# LFO.net
KiCad netlist of a schematic drawn in EAGLE
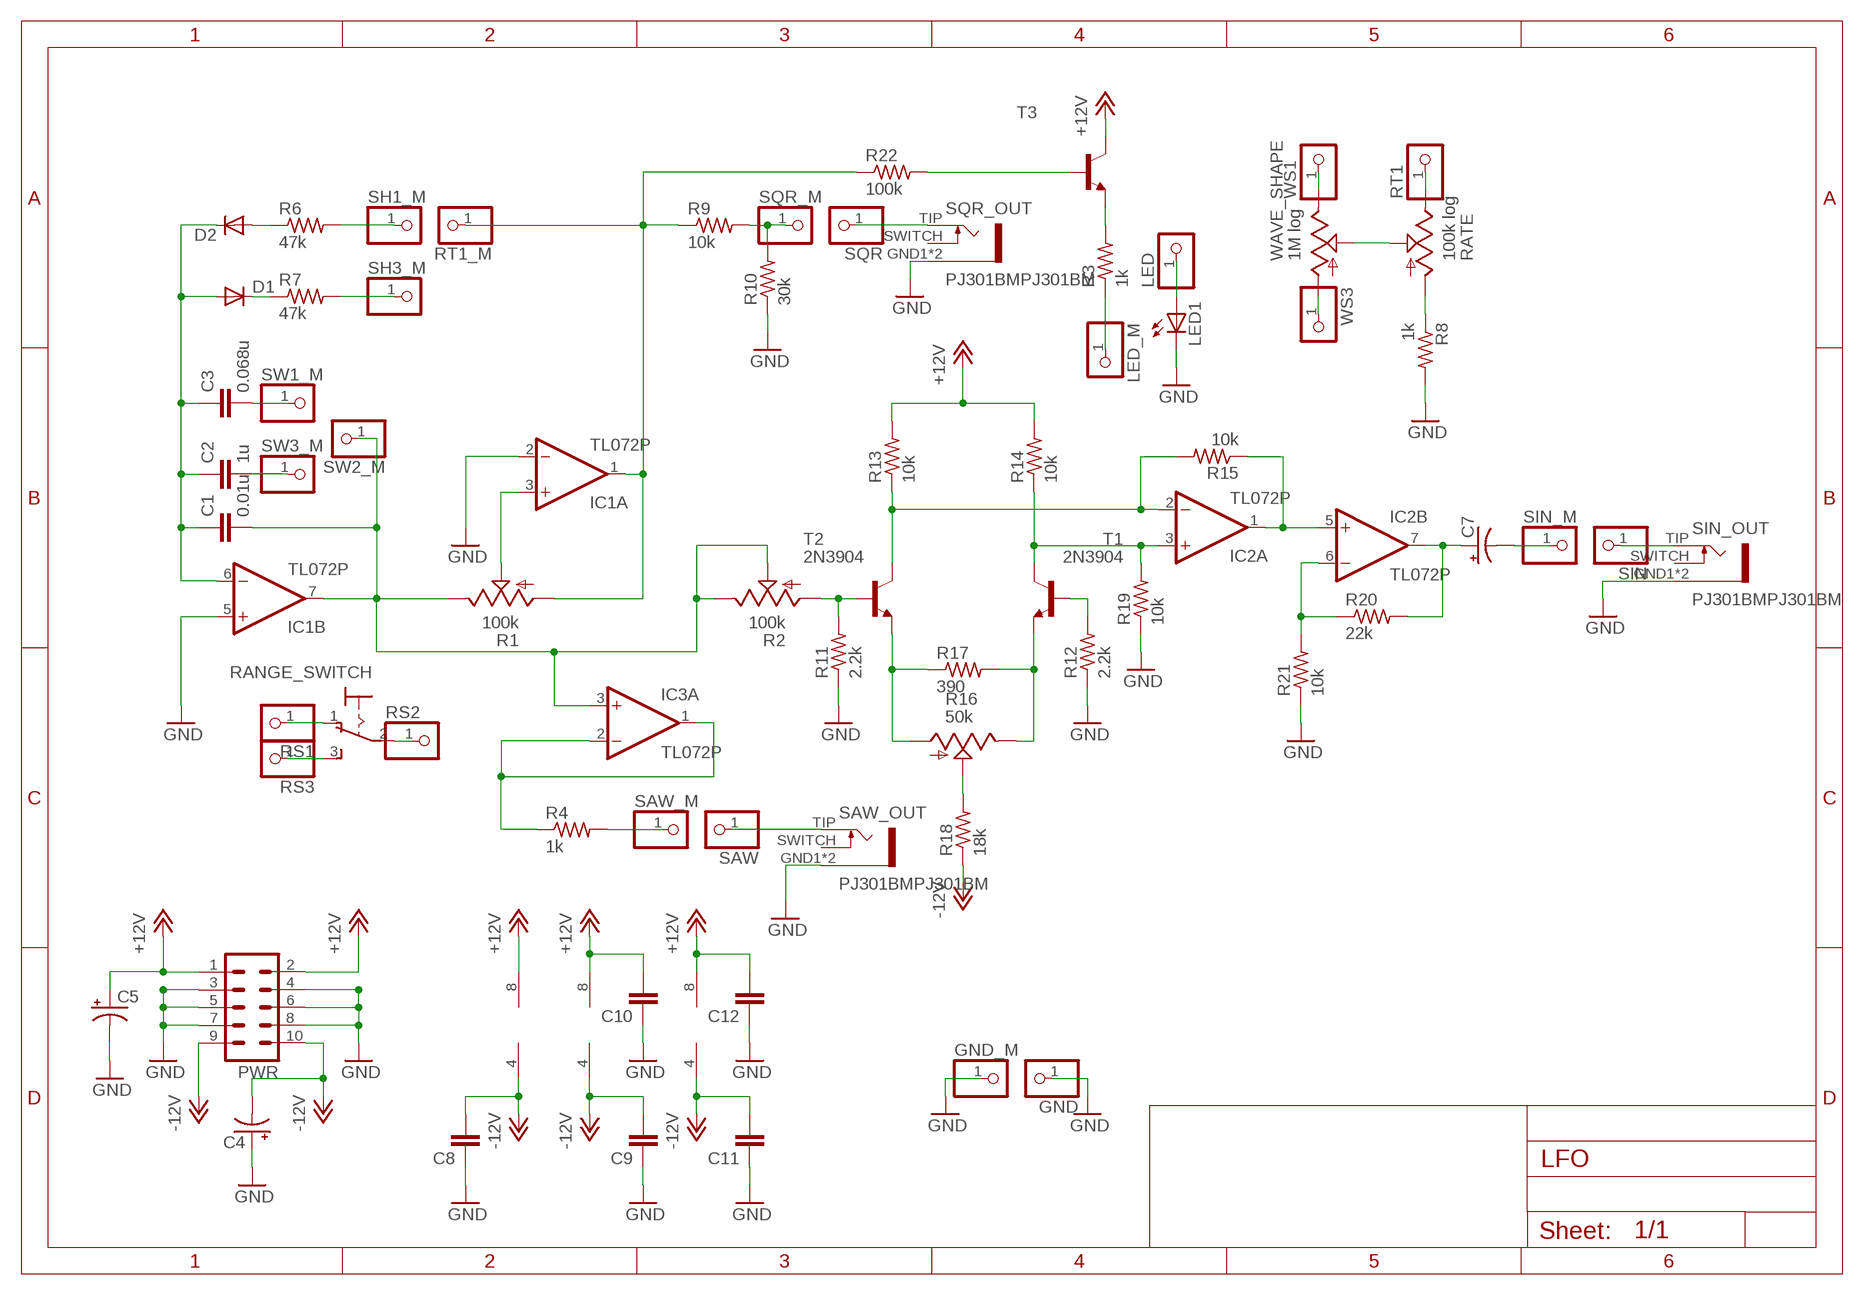
[diagram p0: schematic, sheet 1]

(export (version "E")
  (design (tool "Eeschema 10.0.6"))
  (components
    (comp (ref "C1")
      (value "0.01u")
      (footprint "eagle-import:C050-025X075")
      (libsource (lib "eagle-import") (part "C-EU050-025X075"))
    )
    (comp (ref "C2")
      (value "1u")
      (footprint "eagle-import:C050-025X075")
      (libsource (lib "eagle-import") (part "C-EU050-025X075"))
    )
    (comp (ref "C3")
      (value "0.068u")
      (footprint "eagle-import:C050-025X075")
      (libsource (lib "eagle-import") (part "C-EU050-025X075"))
    )
    (comp (ref "C4")
      (value "CPOL-USE2.5-5")
      (footprint "eagle-import:E2,5-5")
      (libsource (lib "eagle-import") (part "CPOL-USE2.5-5"))
    )
    (comp (ref "C5")
      (value "CPOL-USE2.5-5")
      (footprint "eagle-import:E2,5-5")
      (libsource (lib "eagle-import") (part "CPOL-USE2.5-5"))
    )
    (comp (ref "C7")
      (value "CPOL-USE2.5-5")
      (footprint "eagle-import:E2,5-5")
      (libsource (lib "eagle-import") (part "CPOL-USE2.5-5"))
    )
    (comp (ref "C8")
      (value "C-EU025-024X044")
      (footprint "eagle-import:C025-024X044")
      (libsource (lib "eagle-import") (part "C-EU025-024X044"))
    )
    (comp (ref "C9")
      (value "C-EU025-024X044")
      (footprint "eagle-import:C025-024X044")
      (libsource (lib "eagle-import") (part "C-EU025-024X044"))
    )
    (comp (ref "C10")
      (value "C-EU025-024X044")
      (footprint "eagle-import:C025-024X044")
      (libsource (lib "eagle-import") (part "C-EU025-024X044"))
    )
    (comp (ref "C11")
      (value "C-EU025-024X044")
      (footprint "eagle-import:C025-024X044")
      (libsource (lib "eagle-import") (part "C-EU025-024X044"))
    )
    (comp (ref "C12")
      (value "C-EU025-024X044")
      (footprint "eagle-import:C025-024X044")
      (libsource (lib "eagle-import") (part "C-EU025-024X044"))
    )
    (comp (ref "D1")
      (value "1N4148DO35-7")
      (footprint "eagle-import:DO35-7")
      (libsource (lib "eagle-import") (part "1N4148DO35-7"))
    )
    (comp (ref "D2")
      (value "1N4148DO35-7")
      (footprint "eagle-import:DO35-7")
      (libsource (lib "eagle-import") (part "1N4148DO35-7"))
    )
    (comp (ref "GND")
      (value "PINHD-1X1")
      (footprint "eagle-import:1X01")
      (libsource (lib "eagle-import") (part "PINHD-1X1"))
    )
    (comp (ref "GND_M")
      (value "PINHD-1X1")
      (footprint "eagle-import:1X01")
      (libsource (lib "eagle-import") (part "PINHD-1X1"))
    )
    (comp (ref "IC1")
      (value "TL072P")
      (footprint "eagle-import:DIL08")
      (libsource (lib "eagle-import") (part "TL072P"))
    )
    (comp (ref "IC2")
      (value "TL072P")
      (footprint "eagle-import:DIL08")
      (libsource (lib "eagle-import") (part "TL072P"))
    )
    (comp (ref "IC3")
      (value "TL072P")
      (footprint "eagle-import:DIL08")
      (libsource (lib "eagle-import") (part "TL072P"))
    )
    (comp (ref "LED")
      (value "PINHD-1X1")
      (footprint "eagle-import:1X01")
      (libsource (lib "eagle-import") (part "PINHD-1X1"))
    )
    (comp (ref "LED1")
      (value "LED5MM")
      (footprint "eagle-import:LED5MM")
      (libsource (lib "eagle-import") (part "LED5MM"))
    )
    (comp (ref "LED_M")
      (value "PINHD-1X1")
      (footprint "eagle-import:1X01")
      (libsource (lib "eagle-import") (part "PINHD-1X1"))
    )
    (comp (ref "PWR")
      (value "ML10")
      (footprint "eagle-import:ML10")
      (libsource (lib "eagle-import") (part "ML10"))
    )
    (comp (ref "R1")
      (value "100k")
      (footprint "eagle-import:RJ9W")
      (libsource (lib "eagle-import") (part "TRIM_US-RJ9W"))
    )
    (comp (ref "R2")
      (value "100k")
      (footprint "eagle-import:RJ9W")
      (libsource (lib "eagle-import") (part "TRIM_US-RJ9W"))
    )
    (comp (ref "R3")
      (value "1k")
      (footprint "eagle-import:0207_10")
      (libsource (lib "eagle-import") (part "R-US_0207/10"))
    )
    (comp (ref "R4")
      (value "1k")
      (footprint "eagle-import:0207_2V")
      (libsource (lib "eagle-import") (part "R-US_0207/2V"))
    )
    (comp (ref "R6")
      (value "47k")
      (footprint "eagle-import:0207_10")
      (libsource (lib "eagle-import") (part "R-US_0207/10"))
    )
    (comp (ref "R7")
      (value "47k")
      (footprint "eagle-import:0207_10")
      (libsource (lib "eagle-import") (part "R-US_0207/10"))
    )
    (comp (ref "R8")
      (value "1k")
      (footprint "eagle-import:0207_10")
      (libsource (lib "eagle-import") (part "R-US_0207/10"))
    )
    (comp (ref "R9")
      (value "10k")
      (footprint "eagle-import:0207_10")
      (libsource (lib "eagle-import") (part "R-US_0207/10"))
    )
    (comp (ref "R10")
      (value "30k")
      (footprint "eagle-import:0207_10")
      (libsource (lib "eagle-import") (part "R-US_0207/10"))
    )
    (comp (ref "R11")
      (value "2.2k")
      (footprint "eagle-import:0207_10")
      (libsource (lib "eagle-import") (part "R-US_0207/10"))
    )
    (comp (ref "R12")
      (value "2.2k")
      (footprint "eagle-import:0207_10")
      (libsource (lib "eagle-import") (part "R-US_0207/10"))
    )
    (comp (ref "R13")
      (value "10k")
      (footprint "eagle-import:0207_10")
      (libsource (lib "eagle-import") (part "R-US_0207/10"))
    )
    (comp (ref "R14")
      (value "10k")
      (footprint "eagle-import:0207_2V")
      (libsource (lib "eagle-import") (part "R-US_0207/2V"))
    )
    (comp (ref "R15")
      (value "10k")
      (footprint "eagle-import:0207_2V")
      (libsource (lib "eagle-import") (part "R-US_0207/2V"))
    )
    (comp (ref "R16")
      (value "50k")
      (footprint "eagle-import:RJ9W")
      (libsource (lib "eagle-import") (part "TRIM_US-RJ9W"))
    )
    (comp (ref "R17")
      (value "390")
      (footprint "eagle-import:0207_10")
      (libsource (lib "eagle-import") (part "R-US_0207/10"))
    )
    (comp (ref "R18")
      (value "18k")
      (footprint "eagle-import:0207_10")
      (libsource (lib "eagle-import") (part "R-US_0207/10"))
    )
    (comp (ref "R19")
      (value "10k")
      (footprint "eagle-import:0207_2V")
      (libsource (lib "eagle-import") (part "R-US_0207/2V"))
    )
    (comp (ref "R20")
      (value "22k")
      (footprint "eagle-import:0207_2V")
      (libsource (lib "eagle-import") (part "R-US_0207/2V"))
    )
    (comp (ref "R21")
      (value "10k")
      (footprint "eagle-import:0207_2V")
      (libsource (lib "eagle-import") (part "R-US_0207/2V"))
    )
    (comp (ref "R22")
      (value "100k")
      (footprint "eagle-import:0207_10")
      (libsource (lib "eagle-import") (part "R-US_0207/10"))
    )
    (comp (ref "RANGE_SWITCH")
      (value "M9040P")
      (footprint "eagle-import:M9040P")
      (libsource (lib "eagle-import") (part "M9040P"))
    )
    (comp (ref "RATE")
      (value "100k log")
      (footprint "eagle-import:EVUF")
      (libsource (lib "eagle-import") (part "ALPHA-9MMA"))
    )
    (comp (ref "RS1")
      (value "PINHD-1X1")
      (footprint "eagle-import:1X01")
      (libsource (lib "eagle-import") (part "PINHD-1X1"))
    )
    (comp (ref "RS2")
      (value "PINHD-1X1")
      (footprint "eagle-import:1X01")
      (libsource (lib "eagle-import") (part "PINHD-1X1"))
    )
    (comp (ref "RS3")
      (value "PINHD-1X1")
      (footprint "eagle-import:1X01")
      (libsource (lib "eagle-import") (part "PINHD-1X1"))
    )
    (comp (ref "RT1")
      (value "PINHD-1X1")
      (footprint "eagle-import:1X01")
      (libsource (lib "eagle-import") (part "PINHD-1X1"))
    )
    (comp (ref "RT1_M")
      (value "PINHD-1X1")
      (footprint "eagle-import:1X01")
      (libsource (lib "eagle-import") (part "PINHD-1X1"))
    )
    (comp (ref "SAW")
      (value "PINHD-1X1")
      (footprint "eagle-import:1X01")
      (libsource (lib "eagle-import") (part "PINHD-1X1"))
    )
    (comp (ref "SAW_M")
      (value "PINHD-1X1")
      (footprint "eagle-import:1X01")
      (libsource (lib "eagle-import") (part "PINHD-1X1"))
    )
    (comp (ref "SAW_OUT")
      (value "PJ301BMPJ301BM")
      (footprint "eagle-import:PJ301BM")
      (libsource (lib "eagle-import") (part "PJ301BMPJ301BM"))
    )
    (comp (ref "SH1_M")
      (value "PINHD-1X1")
      (footprint "eagle-import:1X01")
      (libsource (lib "eagle-import") (part "PINHD-1X1"))
    )
    (comp (ref "SH3_M")
      (value "PINHD-1X1")
      (footprint "eagle-import:1X01")
      (libsource (lib "eagle-import") (part "PINHD-1X1"))
    )
    (comp (ref "SIN")
      (value "PINHD-1X1")
      (footprint "eagle-import:1X01")
      (libsource (lib "eagle-import") (part "PINHD-1X1"))
    )
    (comp (ref "SIN_M")
      (value "PINHD-1X1")
      (footprint "eagle-import:1X01")
      (libsource (lib "eagle-import") (part "PINHD-1X1"))
    )
    (comp (ref "SIN_OUT")
      (value "PJ301BMPJ301BM")
      (footprint "eagle-import:PJ301BM")
      (libsource (lib "eagle-import") (part "PJ301BMPJ301BM"))
    )
    (comp (ref "SQR")
      (value "PINHD-1X1")
      (footprint "eagle-import:1X01")
      (libsource (lib "eagle-import") (part "PINHD-1X1"))
    )
    (comp (ref "SQR_M")
      (value "PINHD-1X1")
      (footprint "eagle-import:1X01")
      (libsource (lib "eagle-import") (part "PINHD-1X1"))
    )
    (comp (ref "SQR_OUT")
      (value "PJ301BMPJ301BM")
      (footprint "eagle-import:PJ301BM")
      (libsource (lib "eagle-import") (part "PJ301BMPJ301BM"))
    )
    (comp (ref "SW1_M")
      (value "PINHD-1X1")
      (footprint "eagle-import:1X01")
      (libsource (lib "eagle-import") (part "PINHD-1X1"))
    )
    (comp (ref "SW2_M")
      (value "PINHD-1X1")
      (footprint "eagle-import:1X01")
      (libsource (lib "eagle-import") (part "PINHD-1X1"))
    )
    (comp (ref "SW3_M")
      (value "PINHD-1X1")
      (footprint "eagle-import:1X01")
      (libsource (lib "eagle-import") (part "PINHD-1X1"))
    )
    (comp (ref "T1")
      (value "2N3904")
      (footprint "eagle-import:TO92")
      (libsource (lib "eagle-import") (part "2N3904"))
    )
    (comp (ref "T2")
      (value "2N3904")
      (footprint "eagle-import:TO92")
      (libsource (lib "eagle-import") (part "2N3904"))
    )
    (comp (ref "T3")
      (value "BC550-NPN-TO92-CBE")
      (footprint "eagle-import:TO92-CBE")
      (libsource (lib "eagle-import") (part "-NPN-TO92-CBEBC550"))
    )
    (comp (ref "WAVE_SHAPE")
      (value "1M log")
      (footprint "eagle-import:EVUF")
      (libsource (lib "eagle-import") (part "ALPHA-9MMA"))
    )
    (comp (ref "WS1")
      (value "PINHD-1X1")
      (footprint "eagle-import:1X01")
      (libsource (lib "eagle-import") (part "PINHD-1X1"))
    )
    (comp (ref "WS3")
      (value "PINHD-1X1")
      (footprint "eagle-import:1X01")
      (libsource (lib "eagle-import") (part "PINHD-1X1"))
    )
  )
  (nets
    (net (code "1") (name "+12V") (class "Default")
      (node (ref "C10") (pin "2") (pinfunction "2_2") (pintype "passive"))
      (node (ref "C12") (pin "2") (pinfunction "2_2") (pintype "passive"))
      (node (ref "C5") (pin "+") (pinfunction "+_+") (pintype "passive"))
      (node (ref "IC1") (pin "8") (pinfunction "V+_8") (pintype "power_in"))
      (node (ref "IC2") (pin "8") (pinfunction "V+_8") (pintype "power_in"))
      (node (ref "IC3") (pin "8") (pinfunction "V+_8") (pintype "power_in"))
      (node (ref "PWR") (pin "1") (pinfunction "1_1") (pintype "passive"))
      (node (ref "PWR") (pin "2") (pinfunction "2_2") (pintype "passive"))
      (node (ref "R13") (pin "2") (pinfunction "2_2") (pintype "passive"))
      (node (ref "R14") (pin "2") (pinfunction "2_2") (pintype "passive"))
      (node (ref "T3") (pin "C") (pinfunction "C_C") (pintype "passive"))
    )
    (net (code "2") (name "-12V") (class "Default")
      (node (ref "C11") (pin "2") (pinfunction "2_2") (pintype "passive"))
      (node (ref "C4") (pin "-") (pinfunction "-_-") (pintype "passive"))
      (node (ref "C8") (pin "2") (pinfunction "2_2") (pintype "passive"))
      (node (ref "C9") (pin "2") (pinfunction "2_2") (pintype "passive"))
      (node (ref "IC1") (pin "4") (pinfunction "V-_4") (pintype "power_in"))
      (node (ref "IC2") (pin "4") (pinfunction "V-_4") (pintype "power_in"))
      (node (ref "IC3") (pin "4") (pinfunction "V-_4") (pintype "power_in"))
      (node (ref "PWR") (pin "10") (pinfunction "10_10") (pintype "passive"))
      (node (ref "PWR") (pin "9") (pinfunction "9_9") (pintype "passive"))
      (node (ref "R18") (pin "1") (pinfunction "1_1") (pintype "passive"))
    )
    (net (code "3") (name "GND") (class "Default")
      (node (ref "C10") (pin "1") (pinfunction "1_1") (pintype "passive"))
      (node (ref "C11") (pin "1") (pinfunction "1_1") (pintype "passive"))
      (node (ref "C12") (pin "1") (pinfunction "1_1") (pintype "passive"))
      (node (ref "C4") (pin "+") (pinfunction "+_+") (pintype "passive"))
      (node (ref "C5") (pin "-") (pinfunction "-_-") (pintype "passive"))
      (node (ref "C8") (pin "1") (pinfunction "1_1") (pintype "passive"))
      (node (ref "C9") (pin "1") (pinfunction "1_1") (pintype "passive"))
      (node (ref "GND") (pin "1") (pinfunction "1_1") (pintype "passive"))
      (node (ref "GND_M") (pin "1") (pinfunction "1_1") (pintype "passive"))
      (node (ref "IC1") (pin "2") (pinfunction "-IN_2") (pintype "input"))
      (node (ref "IC1") (pin "5") (pinfunction "+IN_5") (pintype "input"))
      (node (ref "LED1") (pin "K") (pinfunction "C_K") (pintype "passive"))
      (node (ref "PWR") (pin "3") (pinfunction "3_3") (pintype "passive"))
      (node (ref "PWR") (pin "4") (pinfunction "4_4") (pintype "passive"))
      (node (ref "PWR") (pin "5") (pinfunction "5_5") (pintype "passive"))
      (node (ref "PWR") (pin "6") (pinfunction "6_6") (pintype "passive"))
      (node (ref "PWR") (pin "7") (pinfunction "7_7") (pintype "passive"))
      (node (ref "PWR") (pin "8") (pinfunction "8_8") (pintype "passive"))
      (node (ref "R10") (pin "1") (pinfunction "1_1") (pintype "passive"))
      (node (ref "R11") (pin "1") (pinfunction "1_1") (pintype "passive"))
      (node (ref "R12") (pin "1") (pinfunction "1_1") (pintype "passive"))
      (node (ref "R19") (pin "1") (pinfunction "1_1") (pintype "passive"))
      (node (ref "R21") (pin "1") (pinfunction "1_1") (pintype "passive"))
      (node (ref "R8") (pin "2") (pinfunction "2_2") (pintype "passive"))
      (node (ref "SAW_OUT") (pin "GND1") (pinfunction "5_GND1") (pintype "passive"))
      (node (ref "SAW_OUT") (pin "GND2") (pinfunction "5_GND2") (pintype "passive"))
      (node (ref "SIN_OUT") (pin "GND1") (pinfunction "5_GND1") (pintype "passive"))
      (node (ref "SIN_OUT") (pin "GND2") (pinfunction "5_GND2") (pintype "passive"))
      (node (ref "SQR_OUT") (pin "GND1") (pinfunction "5_GND1") (pintype "passive"))
      (node (ref "SQR_OUT") (pin "GND2") (pinfunction "5_GND2") (pintype "passive"))
    )
    (net (code "4") (name "Net-(C2-Pad2)") (class "Default")
      (node (ref "C2") (pin "2") (pinfunction "2_2") (pintype "passive"))
      (node (ref "SW3_M") (pin "1") (pinfunction "1_1") (pintype "passive"))
    )
    (net (code "5") (name "Net-(C3-Pad2)") (class "Default")
      (node (ref "C3") (pin "2") (pinfunction "2_2") (pintype "passive"))
      (node (ref "SW1_M") (pin "1") (pinfunction "1_1") (pintype "passive"))
    )
    (net (code "6") (name "Net-(C7-Pad-)") (class "Default")
      (node (ref "C7") (pin "-") (pinfunction "-_-") (pintype "passive"))
      (node (ref "SIN_M") (pin "1") (pinfunction "1_1") (pintype "passive"))
    )
    (net (code "7") (name "Net-(D1-PadC)") (class "Default")
      (node (ref "D1") (pin "C") (pinfunction "C_C") (pintype "passive"))
      (node (ref "R7") (pin "1") (pinfunction "1_1") (pintype "passive"))
    )
    (net (code "8") (name "Net-(D2-PadA)") (class "Default")
      (node (ref "D2") (pin "A") (pinfunction "A_A") (pintype "passive"))
      (node (ref "R6") (pin "1") (pinfunction "1_1") (pintype "passive"))
    )
    (net (code "9") (name "Net-(IC1A-+IN)") (class "Default")
      (node (ref "IC1") (pin "3") (pinfunction "+IN_3") (pintype "input"))
      (node (ref "R1") (pin "S") (pinfunction "S_S") (pintype "passive"))
    )
    (net (code "10") (name "Net-(IC1A-OUT)") (class "Default")
      (node (ref "IC1") (pin "1") (pinfunction "OUT_1") (pintype "output"))
      (node (ref "R1") (pin "A") (pinfunction "A_A") (pintype "passive"))
      (node (ref "R22") (pin "1") (pinfunction "1_1") (pintype "passive"))
      (node (ref "R9") (pin "1") (pinfunction "1_1") (pintype "passive"))
      (node (ref "RT1_M") (pin "1") (pinfunction "1_1") (pintype "passive"))
    )
    (net (code "11") (name "Net-(IC1B--IN)") (class "Default")
      (node (ref "C1") (pin "1") (pinfunction "1_1") (pintype "passive"))
      (node (ref "C2") (pin "1") (pinfunction "1_1") (pintype "passive"))
      (node (ref "C3") (pin "1") (pinfunction "1_1") (pintype "passive"))
      (node (ref "D1") (pin "A") (pinfunction "A_A") (pintype "passive"))
      (node (ref "D2") (pin "C") (pinfunction "C_C") (pintype "passive"))
      (node (ref "IC1") (pin "6") (pinfunction "-IN_6") (pintype "input"))
    )
    (net (code "12") (name "Net-(IC1B-OUT)") (class "Default")
      (node (ref "C1") (pin "2") (pinfunction "2_2") (pintype "passive"))
      (node (ref "IC1") (pin "7") (pinfunction "OUT_7") (pintype "output"))
      (node (ref "IC3") (pin "3") (pinfunction "+IN_3") (pintype "input"))
      (node (ref "R1") (pin "E") (pinfunction "E_E") (pintype "passive"))
      (node (ref "R2") (pin "E") (pinfunction "E_E") (pintype "passive"))
      (node (ref "R2") (pin "S") (pinfunction "S_S") (pintype "passive"))
      (node (ref "SW2_M") (pin "1") (pinfunction "1_1") (pintype "passive"))
    )
    (net (code "13") (name "Net-(IC2A-+IN)") (class "Default")
      (node (ref "IC2") (pin "3") (pinfunction "+IN_3") (pintype "input"))
      (node (ref "R14") (pin "1") (pinfunction "1_1") (pintype "passive"))
      (node (ref "R19") (pin "2") (pinfunction "2_2") (pintype "passive"))
      (node (ref "T1") (pin "1") (pinfunction "C_1") (pintype "passive"))
    )
    (net (code "14") (name "Net-(IC2A--IN)") (class "Default")
      (node (ref "IC2") (pin "2") (pinfunction "-IN_2") (pintype "input"))
      (node (ref "R13") (pin "1") (pinfunction "1_1") (pintype "passive"))
      (node (ref "R15") (pin "2") (pinfunction "2_2") (pintype "passive"))
      (node (ref "T2") (pin "1") (pinfunction "C_1") (pintype "passive"))
    )
    (net (code "15") (name "Net-(IC2A-OUT)") (class "Default")
      (node (ref "IC2") (pin "1") (pinfunction "OUT_1") (pintype "output"))
      (node (ref "IC2") (pin "5") (pinfunction "+IN_5") (pintype "input"))
      (node (ref "R15") (pin "1") (pinfunction "1_1") (pintype "passive"))
    )
    (net (code "16") (name "Net-(IC2B--IN)") (class "Default")
      (node (ref "IC2") (pin "6") (pinfunction "-IN_6") (pintype "input"))
      (node (ref "R20") (pin "1") (pinfunction "1_1") (pintype "passive"))
      (node (ref "R21") (pin "2") (pinfunction "2_2") (pintype "passive"))
    )
    (net (code "17") (name "Net-(IC2B-OUT)") (class "Default")
      (node (ref "C7") (pin "+") (pinfunction "+_+") (pintype "passive"))
      (node (ref "IC2") (pin "7") (pinfunction "OUT_7") (pintype "output"))
      (node (ref "R20") (pin "2") (pinfunction "2_2") (pintype "passive"))
    )
    (net (code "18") (name "Net-(IC3A--IN)") (class "Default")
      (node (ref "IC3") (pin "1") (pinfunction "OUT_1") (pintype "output"))
      (node (ref "IC3") (pin "2") (pinfunction "-IN_2") (pintype "input"))
      (node (ref "R4") (pin "1") (pinfunction "1_1") (pintype "passive"))
    )
    (net (code "19") (name "Net-(LED-Pad1)") (class "Default")
      (node (ref "LED") (pin "1") (pinfunction "1_1") (pintype "passive"))
      (node (ref "LED1") (pin "A") (pinfunction "A_A") (pintype "passive"))
    )
    (net (code "20") (name "Net-(LED_M-Pad1)") (class "Default")
      (node (ref "LED_M") (pin "1") (pinfunction "1_1") (pintype "passive"))
      (node (ref "R3") (pin "1") (pinfunction "1_1") (pintype "passive"))
    )
    (net (code "21") (name "Net-(R3-Pad2)") (class "Default")
      (node (ref "R3") (pin "2") (pinfunction "2_2") (pintype "passive"))
      (node (ref "T3") (pin "E") (pinfunction "E_E") (pintype "passive"))
    )
    (net (code "22") (name "Net-(R4-Pad2)") (class "Default")
      (node (ref "R4") (pin "2") (pinfunction "2_2") (pintype "passive"))
      (node (ref "SAW_M") (pin "1") (pinfunction "1_1") (pintype "passive"))
    )
    (net (code "23") (name "Net-(R6-Pad2)") (class "Default")
      (node (ref "R6") (pin "2") (pinfunction "2_2") (pintype "passive"))
      (node (ref "SH1_M") (pin "1") (pinfunction "1_1") (pintype "passive"))
    )
    (net (code "24") (name "Net-(R7-Pad2)") (class "Default")
      (node (ref "R7") (pin "2") (pinfunction "2_2") (pintype "passive"))
      (node (ref "SH3_M") (pin "1") (pinfunction "1_1") (pintype "passive"))
    )
    (net (code "25") (name "Net-(R10-Pad2)") (class "Default")
      (node (ref "R10") (pin "2") (pinfunction "2_2") (pintype "passive"))
      (node (ref "R9") (pin "2") (pinfunction "2_2") (pintype "passive"))
      (node (ref "SQR_M") (pin "1") (pinfunction "1_1") (pintype "passive"))
    )
    (net (code "26") (name "Net-(R16-PadS)") (class "Default")
      (node (ref "R16") (pin "S") (pinfunction "S_S") (pintype "passive"))
      (node (ref "R18") (pin "2") (pinfunction "2_2") (pintype "passive"))
    )
    (net (code "27") (name "Net-(R22-Pad2)") (class "Default")
      (node (ref "R22") (pin "2") (pinfunction "2_2") (pintype "passive"))
      (node (ref "T3") (pin "B") (pinfunction "B_B") (pintype "passive"))
    )
    (net (code "28") (name "Net-(RANGE_SWITCH-O)") (class "Default")
      (node (ref "RANGE_SWITCH") (pin "1") (pinfunction "O_1") (pintype "passive"))
      (node (ref "RS1") (pin "1") (pinfunction "1_1") (pintype "passive"))
    )
    (net (code "29") (name "Net-(RANGE_SWITCH-P)") (class "Default")
      (node (ref "RANGE_SWITCH") (pin "2") (pinfunction "P_2") (pintype "passive"))
      (node (ref "RS2") (pin "1") (pinfunction "1_1") (pintype "passive"))
    )
    (net (code "30") (name "Net-(RANGE_SWITCH-S)") (class "Default")
      (node (ref "RANGE_SWITCH") (pin "3") (pinfunction "S_3") (pintype "passive"))
      (node (ref "RS3") (pin "1") (pinfunction "1_1") (pintype "passive"))
    )
    (net (code "31") (name "Net-(RATE-A)") (class "Default")
      (node (ref "R8") (pin "1") (pinfunction "1_1") (pintype "passive"))
      (node (ref "RATE") (pin "1") (pinfunction "A_1") (pintype "passive"))
    )
    (net (code "32") (name "Net-(RATE-E)") (class "Default")
      (node (ref "RATE") (pin "3") (pinfunction "E_3") (pintype "passive"))
      (node (ref "RT1") (pin "1") (pinfunction "1_1") (pintype "passive"))
    )
    (net (code "33") (name "Net-(RATE-S)") (class "Default")
      (node (ref "RATE") (pin "2") (pinfunction "S_2") (pintype "passive"))
      (node (ref "WAVE_SHAPE") (pin "2") (pinfunction "S_2") (pintype "passive"))
    )
    (net (code "34") (name "Net-(SAW_OUT-3)") (class "Default")
      (node (ref "SAW") (pin "1") (pinfunction "1_1") (pintype "passive"))
      (node (ref "SAW_OUT") (pin "TIP") (pinfunction "3_TIP") (pintype "passive"))
    )
    (net (code "35") (name "Net-(SIN_OUT-3)") (class "Default")
      (node (ref "SIN") (pin "1") (pinfunction "1_1") (pintype "passive"))
      (node (ref "SIN_OUT") (pin "TIP") (pinfunction "3_TIP") (pintype "passive"))
    )
    (net (code "36") (name "Net-(SQR_OUT-3)") (class "Default")
      (node (ref "SQR") (pin "1") (pinfunction "1_1") (pintype "passive"))
      (node (ref "SQR_OUT") (pin "TIP") (pinfunction "3_TIP") (pintype "passive"))
    )
    (net (code "37") (name "Net-(T1-B)") (class "Default")
      (node (ref "R12") (pin "2") (pinfunction "2_2") (pintype "passive"))
      (node (ref "T1") (pin "2") (pinfunction "B_2") (pintype "passive"))
    )
    (net (code "38") (name "Net-(T1-E)") (class "Default")
      (node (ref "R16") (pin "E") (pinfunction "E_E") (pintype "passive"))
      (node (ref "R17") (pin "2") (pinfunction "2_2") (pintype "passive"))
      (node (ref "T1") (pin "3") (pinfunction "E_3") (pintype "passive"))
    )
    (net (code "39") (name "Net-(T2-B)") (class "Default")
      (node (ref "R11") (pin "2") (pinfunction "2_2") (pintype "passive"))
      (node (ref "R2") (pin "A") (pinfunction "A_A") (pintype "passive"))
      (node (ref "T2") (pin "2") (pinfunction "B_2") (pintype "passive"))
    )
    (net (code "40") (name "Net-(T2-E)") (class "Default")
      (node (ref "R16") (pin "A") (pinfunction "A_A") (pintype "passive"))
      (node (ref "R17") (pin "1") (pinfunction "1_1") (pintype "passive"))
      (node (ref "T2") (pin "3") (pinfunction "E_3") (pintype "passive"))
    )
    (net (code "41") (name "Net-(WAVE_SHAPE-A)") (class "Default")
      (node (ref "WAVE_SHAPE") (pin "1") (pinfunction "A_1") (pintype "passive"))
      (node (ref "WS3") (pin "1") (pinfunction "1_1") (pintype "passive"))
    )
    (net (code "42") (name "Net-(WAVE_SHAPE-E)") (class "Default")
      (node (ref "WAVE_SHAPE") (pin "3") (pinfunction "E_3") (pintype "passive"))
      (node (ref "WS1") (pin "1") (pinfunction "1_1") (pintype "passive"))
    )
    (net (code "43") (name "unconnected-(SAW_OUT-4-PadSWITCH)") (class "Default")
      (node (ref "SAW_OUT") (pin "SWITCH") (pinfunction "4_SWITCH") (pintype "passive"))
    )
    (net (code "44") (name "unconnected-(SIN_OUT-4-PadSWITCH)") (class "Default")
      (node (ref "SIN_OUT") (pin "SWITCH") (pinfunction "4_SWITCH") (pintype "passive"))
    )
    (net (code "45") (name "unconnected-(SQR_OUT-4-PadSWITCH)") (class "Default")
      (node (ref "SQR_OUT") (pin "SWITCH") (pinfunction "4_SWITCH") (pintype "passive"))
    )
  )
)
